# Sheet1.net
KiCad netlist of a schematic drawn in Altium Designer
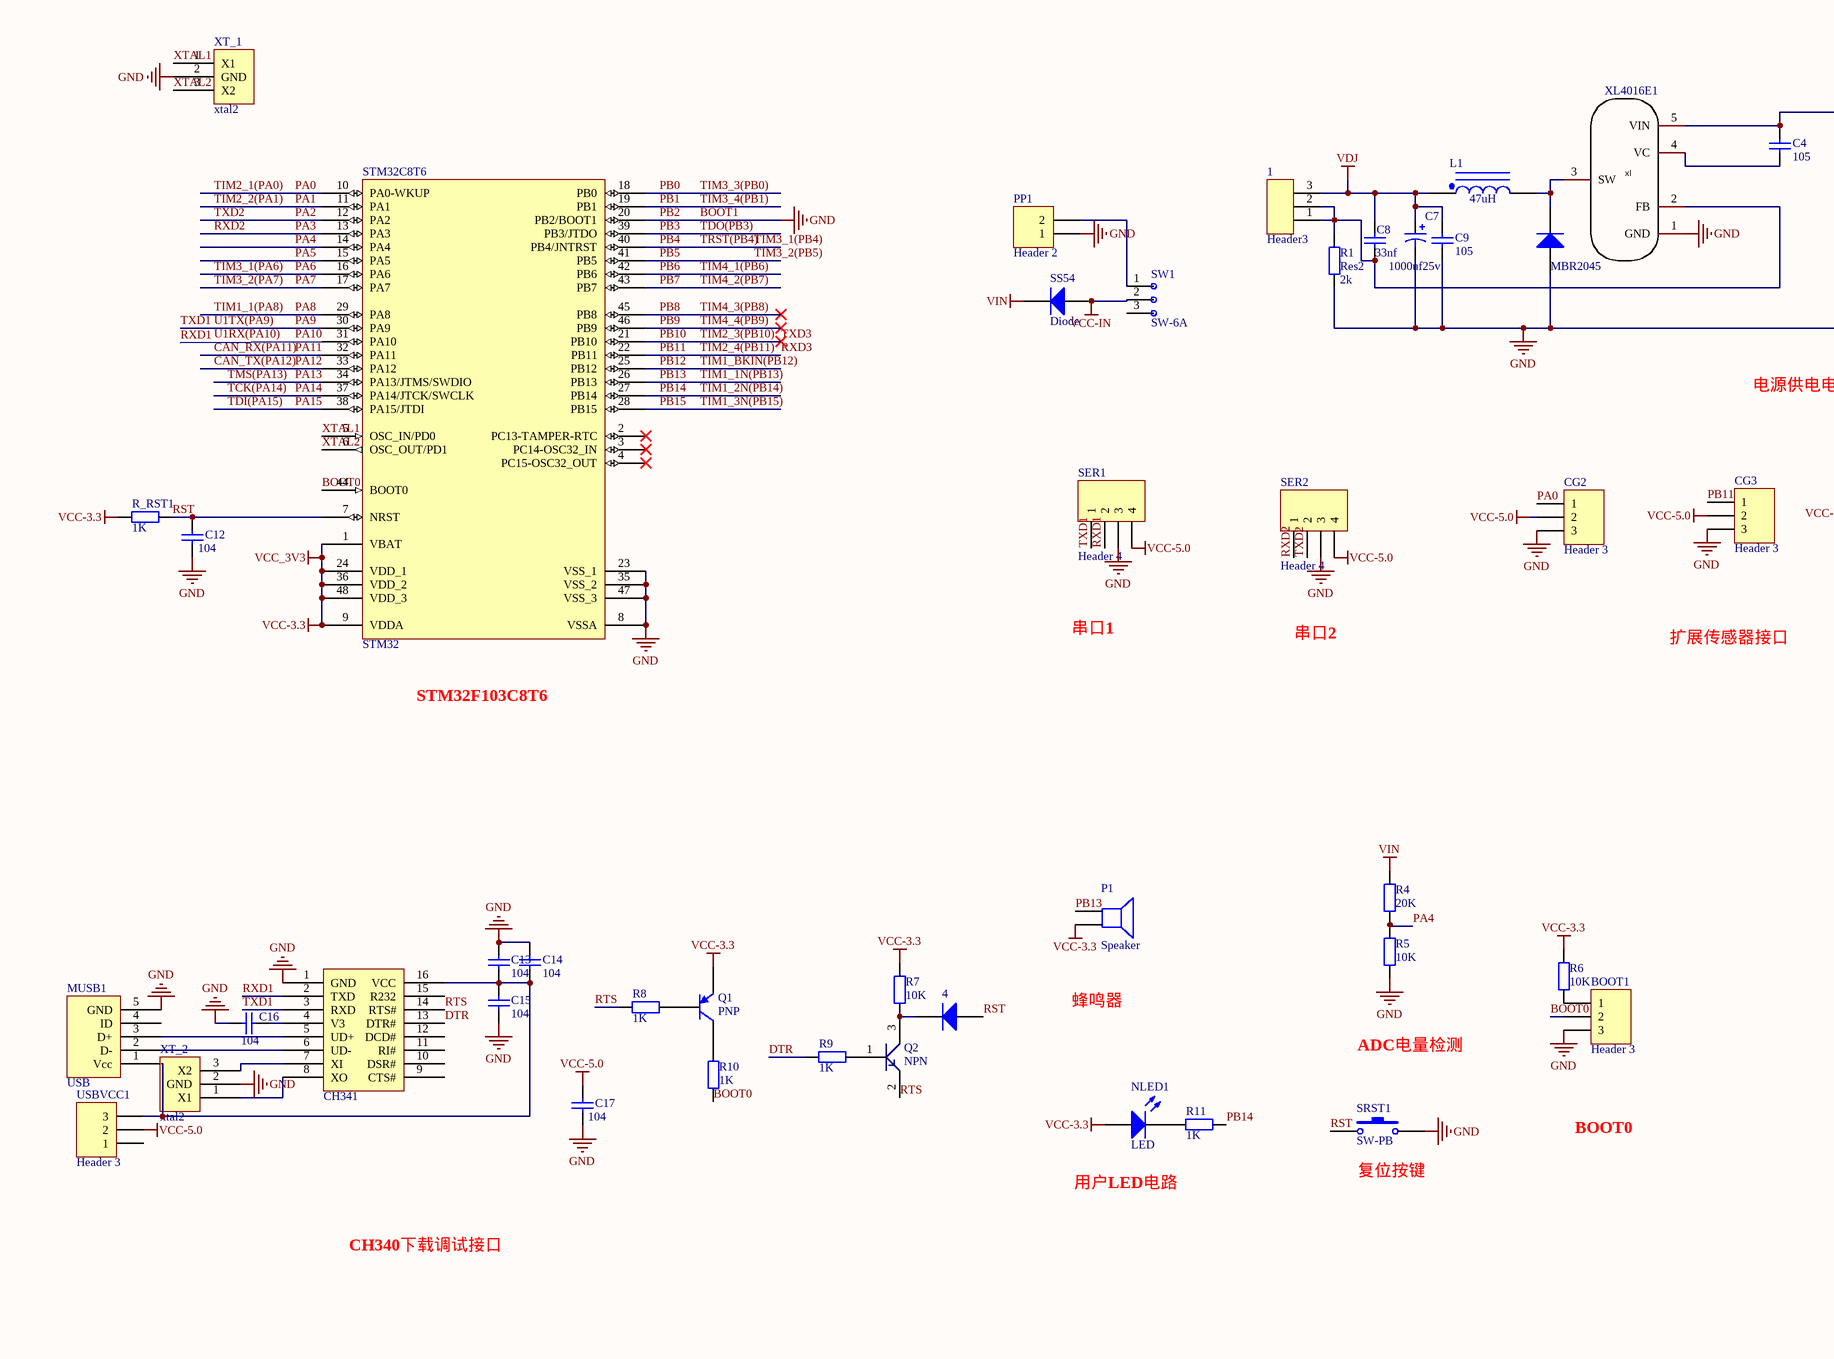
[diagram p0: Sheet1.SchDoc, left]
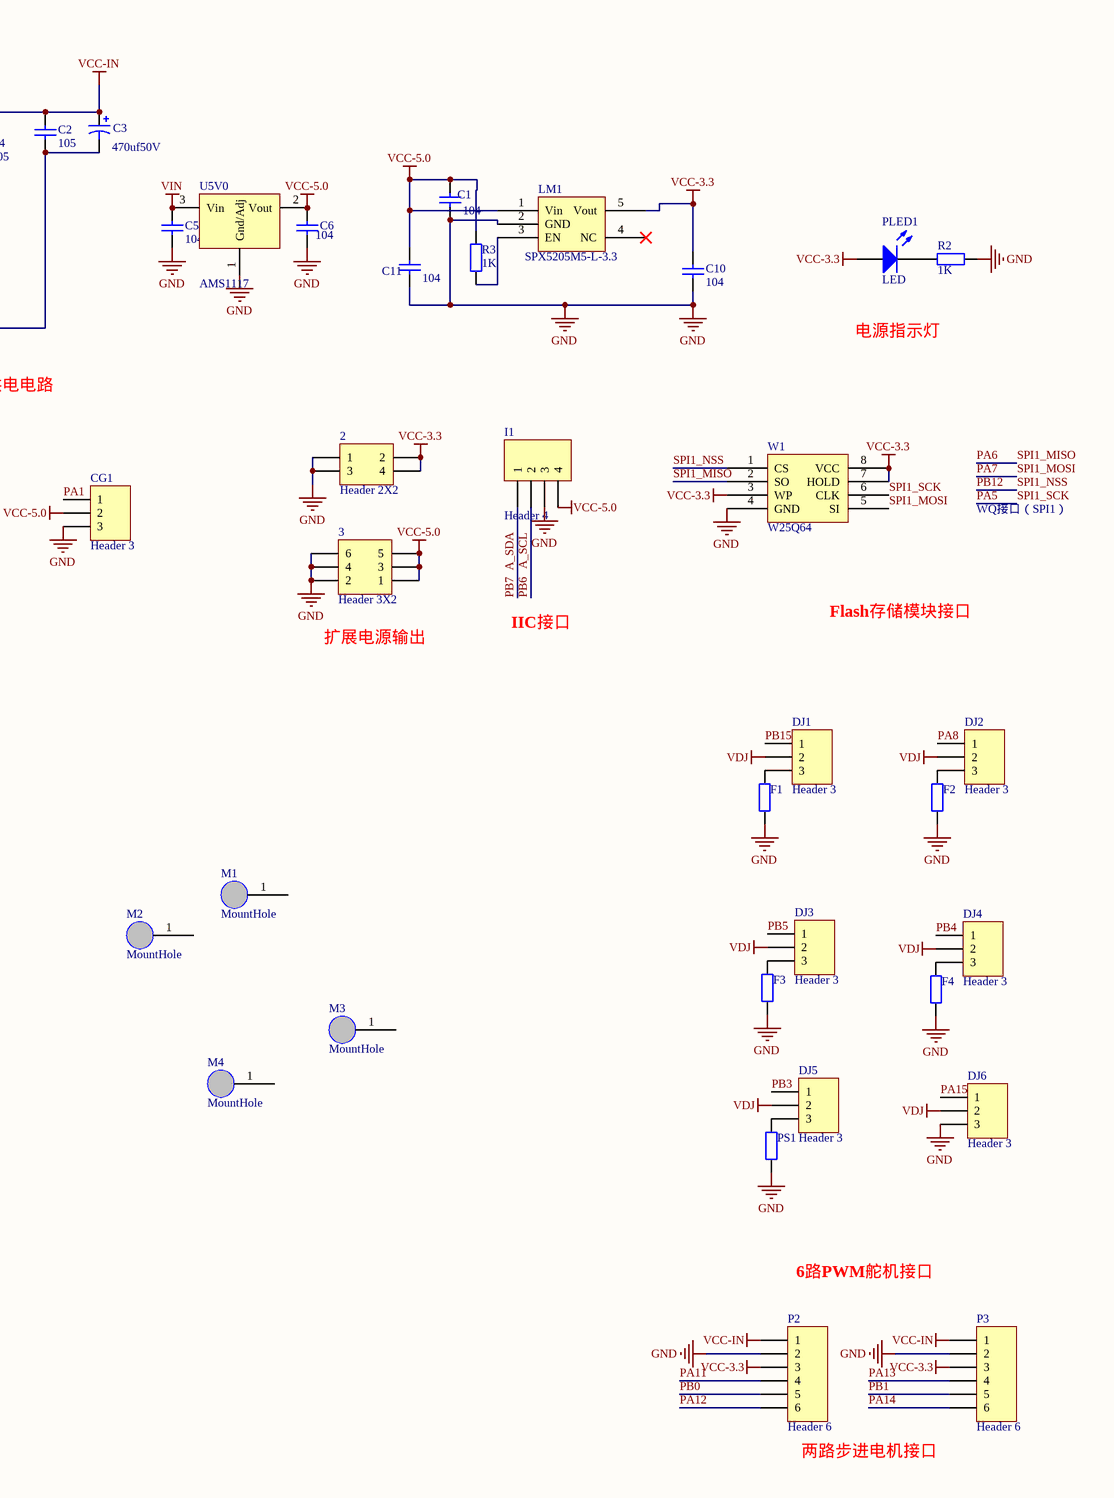
[diagram p1: Sheet1.SchDoc, right]

(export (version "E")
  (design (tool "Eeschema 10.0.6"))
  (components
    (comp (ref "1") (value "Header3") (footprint "pot（长方形）") (libsource (lib "MY-SCH") (part "Header3")))
    (comp (ref "2")
      (value "Header 2X2")
      (footprint "HDR2X2")
      (description "Header, 2-Pin, Dual row")
      (fields (field (name "PUBLISHER") "Altium Limited"))
      (libsource (lib "Miscellaneous Connectors") (part "Header 2X2"))
    )
    (comp (ref "3")
      (value "Header 3X2")
      (footprint "HDR2X3")
      (description "Header, 3-Pin, Dual row")
      (fields (field (name "PUBLISHER") "Altium Limited"))
      (libsource (lib "Miscellaneous Connectors") (part "Header 3X2"))
    )
    (comp (ref "4")
      (value "Diode 1N4007")
      (footprint "0805L")
      (description "1 Amp General Purpose Rectifier")
      (fields (field (name "PUBLISHER") "Altium Limited"))
      (libsource (lib "MY-SCH") (part "Diode 1N4007"))
    )
    (comp (ref "BOOT1")
      (value "Header 3")
      (footprint "HDR1X3")
      (description "Header, 3-Pin")
      (fields (field (name "PUBLISHER") "Altium Limited"))
      (libsource (lib "Miscellaneous Connectors") (part "Header 3"))
    )
    (comp (ref "C1")
      (value "104")
      (footprint "0603C")
      (description "Capacitor")
      (fields (field (name "Comment") "Cap") (field (name "PUBLISHER") "Altium Limited"))
      (libsource (lib "Miscellaneous Devices") (part "Cap"))
    )
    (comp (ref "C2")
      (value "105")
      (footprint "0603C")
      (description "Capacitor")
      (fields (field (name "Comment") "Cap") (field (name "PUBLISHER") "Altium Limited"))
      (libsource (lib "Miscellaneous Devices") (part "Cap"))
    )
    (comp (ref "C3")
      (value "470uf50V")
      (footprint "CAP_10_TIE")
      (description "Polarized Capacitor (Radial)")
      (fields (field (name "Comment") "Cap Pol1") (field (name "PUBLISHER") "Altium Limited"))
      (libsource (lib "Miscellaneous Devices") (part "Cap Pol1"))
    )
    (comp (ref "C4")
      (value "105")
      (footprint "0603C")
      (description "Capacitor")
      (fields (field (name "Comment") "Cap") (field (name "PUBLISHER") "Altium Limited"))
      (libsource (lib "Miscellaneous Devices") (part "Cap"))
    )
    (comp (ref "C5")
      (value "104")
      (footprint "0603C")
      (description "Capacitor")
      (fields (field (name "Comment") "Cap") (field (name "PUBLISHER") "Altium Limited"))
      (libsource (lib "Miscellaneous Devices") (part "Cap"))
    )
    (comp (ref "C6")
      (value "104")
      (footprint "0603C")
      (description "Capacitor")
      (fields (field (name "Comment") "Cap") (field (name "PUBLISHER") "Altium Limited"))
      (libsource (lib "Miscellaneous Devices") (part "Cap"))
    )
    (comp (ref "C7") (value "1000uf25v") (footprint "cap_6.3_tie") (libsource (lib "集成库") (part "Cap_Pol")))
    (comp (ref "C8")
      (value "33nf")
      (footprint "0603C")
      (description "Capacitor")
      (fields (field (name "Comment") "Cap") (field (name "PUBLISHER") "Altium Limited"))
      (libsource (lib "Miscellaneous Devices") (part "Cap"))
    )
    (comp (ref "C9")
      (value "105")
      (footprint "0603C")
      (description "Capacitor")
      (fields (field (name "Comment") "Cap") (field (name "PUBLISHER") "Altium Limited"))
      (libsource (lib "Miscellaneous Devices") (part "Cap"))
    )
    (comp (ref "C10")
      (value "104")
      (footprint "0603C")
      (description "Capacitor")
      (fields (field (name "Comment") "Cap") (field (name "PUBLISHER") "Altium Limited"))
      (libsource (lib "Miscellaneous Devices") (part "Cap"))
    )
    (comp (ref "C11")
      (value "104")
      (footprint "0603C")
      (description "Capacitor")
      (fields (field (name "Comment") "Cap") (field (name "PUBLISHER") "Altium Limited"))
      (libsource (lib "Miscellaneous Devices") (part "Cap"))
    )
    (comp (ref "C12")
      (value "104")
      (footprint "0603C")
      (description "Capacitor")
      (fields (field (name "Comment") "Cap") (field (name "PUBLISHER") "Altium Limited"))
      (libsource (lib "Miscellaneous Devices") (part "Cap"))
    )
    (comp (ref "C13")
      (value "104")
      (footprint "0603C")
      (description "Capacitor")
      (fields (field (name "Comment") "Cap") (field (name "PUBLISHER") "Altium Limited"))
      (libsource (lib "Miscellaneous Devices") (part "Cap"))
    )
    (comp (ref "C14")
      (value "104")
      (footprint "0603C")
      (description "Capacitor")
      (fields (field (name "Comment") "Cap") (field (name "PUBLISHER") "Altium Limited"))
      (libsource (lib "Miscellaneous Devices") (part "Cap"))
    )
    (comp (ref "C15")
      (value "104")
      (footprint "0603C")
      (description "Capacitor")
      (fields (field (name "Comment") "Cap") (field (name "PUBLISHER") "Altium Limited"))
      (libsource (lib "Miscellaneous Devices") (part "Cap"))
    )
    (comp (ref "C16")
      (value "104")
      (footprint "0603C")
      (description "Capacitor")
      (fields (field (name "Comment") "Cap") (field (name "PUBLISHER") "Altium Limited"))
      (libsource (lib "Miscellaneous Devices") (part "Cap"))
    )
    (comp (ref "C17")
      (value "104")
      (footprint "0603C")
      (description "Capacitor")
      (fields (field (name "Comment") "Cap") (field (name "PUBLISHER") "Altium Limited"))
      (libsource (lib "Miscellaneous Devices") (part "Cap"))
    )
    (comp (ref "CG1")
      (value "Header 3")
      (footprint "HDR1X3")
      (description "Header, 3-Pin")
      (fields (field (name "PUBLISHER") "Altium Limited"))
      (libsource (lib "Miscellaneous Connectors") (part "Header 3"))
    )
    (comp (ref "CG2")
      (value "Header 3")
      (footprint "HDR1X3")
      (description "Header, 3-Pin")
      (fields (field (name "PUBLISHER") "Altium Limited"))
      (libsource (lib "Miscellaneous Connectors") (part "Header 3"))
    )
    (comp (ref "CG3")
      (value "Header 3")
      (footprint "HDR1X3")
      (description "Header, 3-Pin")
      (fields (field (name "PUBLISHER") "Altium Limited"))
      (libsource (lib "Miscellaneous Connectors") (part "Header 3"))
    )
    (comp (ref "CH1") (value "CH341") (footprint "SOP16") (libsource (lib "DYS.SCHL1") (part "CH341")))
    (comp (ref "DJ1")
      (value "Header 3")
      (footprint "HDR1X3")
      (description "Header, 3-Pin")
      (fields (field (name "PUBLISHER") "Altium Limited"))
      (libsource (lib "Miscellaneous Connectors") (part "Header 3"))
    )
    (comp (ref "DJ2")
      (value "Header 3")
      (footprint "HDR1X3")
      (description "Header, 3-Pin")
      (fields (field (name "PUBLISHER") "Altium Limited"))
      (libsource (lib "Miscellaneous Connectors") (part "Header 3"))
    )
    (comp (ref "DJ3")
      (value "Header 3")
      (footprint "HDR1X3")
      (description "Header, 3-Pin")
      (fields (field (name "PUBLISHER") "Altium Limited"))
      (libsource (lib "Miscellaneous Connectors") (part "Header 3"))
    )
    (comp (ref "DJ4")
      (value "Header 3")
      (footprint "HDR1X3")
      (description "Header, 3-Pin")
      (fields (field (name "PUBLISHER") "Altium Limited"))
      (libsource (lib "Miscellaneous Connectors") (part "Header 3"))
    )
    (comp (ref "DJ5")
      (value "Header 3")
      (footprint "HDR1X3")
      (description "Header, 3-Pin")
      (fields (field (name "PUBLISHER") "Altium Limited"))
      (libsource (lib "Miscellaneous Connectors") (part "Header 3"))
    )
    (comp (ref "DJ6")
      (value "Header 3")
      (footprint "HDR1X3")
      (description "Header, 3-Pin")
      (fields (field (name "PUBLISHER") "Altium Limited"))
      (libsource (lib "Miscellaneous Connectors") (part "Header 3"))
    )
    (comp (ref "F1")
      (value "Res2")
      (footprint "0805R")
      (description "Resistor")
      (fields (field (name "PUBLISHER") "Altium Limited"))
      (libsource (lib "Miscellaneous Devices") (part "Res2"))
    )
    (comp (ref "F2")
      (value "Res2")
      (footprint "0805R")
      (description "Resistor")
      (fields (field (name "PUBLISHER") "Altium Limited"))
      (libsource (lib "Miscellaneous Devices") (part "Res2"))
    )
    (comp (ref "F3")
      (value "Res2")
      (footprint "0805R")
      (description "Resistor")
      (fields (field (name "PUBLISHER") "Altium Limited"))
      (libsource (lib "Miscellaneous Devices") (part "Res2"))
    )
    (comp (ref "F4")
      (value "Res2")
      (footprint "0805R")
      (description "Resistor")
      (fields (field (name "PUBLISHER") "Altium Limited"))
      (libsource (lib "Miscellaneous Devices") (part "Res2"))
    )
    (comp (ref "I1")
      (value "Header 4")
      (footprint "HDR1X4")
      (description "Header, 4-Pin")
      (fields (field (name "PUBLISHER") "Altium Limited"))
      (libsource (lib "Miscellaneous Connectors") (part "Header 4"))
    )
    (comp (ref "L1")
      (value "47uH")
      (footprint "L_8x15")
      (description "Magnetic-Core Inductor with Winding Polarity Marking")
      (fields (field (name "Comment") "Inductor Iron Dot") (field (name "PUBLISHER") "Altium Limited"))
      (libsource (lib "Miscellaneous Devices") (part "Inductor Iron Dot"))
    )
    (comp (ref "LM1")
      (value "SPX5205M5-L-3.3")
      (footprint "spx520")
      (libsource (lib "DYS.SCHL1") (part "SPX5205M5-L-5-0"))
    )
    (comp (ref "M1")
      (value "MountHole")
      (footprint "M3-MountSlot")
      (description "固定孔")
      (libsource (lib "DRV8701E 双驱V1.1 集成封装库") (part "MountHole"))
    )
    (comp (ref "M2")
      (value "MountHole")
      (footprint "M3-MountSlot")
      (description "固定孔")
      (libsource (lib "DRV8701E 双驱V1.1 集成封装库") (part "MountHole"))
    )
    (comp (ref "M3")
      (value "MountHole")
      (footprint "M3-MountSlot")
      (description "固定孔")
      (libsource (lib "DRV8701E 双驱V1.1 集成封装库") (part "MountHole"))
    )
    (comp (ref "M4")
      (value "MountHole")
      (footprint "M3-MountSlot")
      (description "固定孔")
      (libsource (lib "DRV8701E 双驱V1.1 集成封装库") (part "MountHole"))
    )
    (comp (ref "MBR2045")
      (value "Diode 1N4007")
      (footprint "SS54")
      (description "1 Amp General Purpose Rectifier")
      (fields (field (name "PUBLISHER") "Altium Limited"))
      (libsource (lib "MY-SCH") (part "Diode 1N4007"))
    )
    (comp (ref "MUSB1") (value "USB") (footprint "microMINIusb 2") (libsource (lib "DYS.SCHL1") (part "USB")))
    (comp (ref "NLED1") (value "LED") (footprint "0603L") (libsource (lib "MY-SCH") (part "LED")))
    (comp (ref "P1")
      (value "Speaker")
      (footprint "beep_9mm")
      (description "Loudspeaker")
      (fields (field (name "PUBLISHER") "Altium Limited"))
      (libsource (lib "Miscellaneous Devices") (part "Speaker"))
    )
    (comp (ref "P2")
      (value "Header 6")
      (footprint "HDR1X6")
      (description "Header, 6-Pin")
      (fields (field (name "PUBLISHER") "Altium Limited"))
      (libsource (lib "Miscellaneous Connectors") (part "Header 6"))
    )
    (comp (ref "P3")
      (value "Header 6")
      (footprint "HDR1X6")
      (description "Header, 6-Pin")
      (fields (field (name "PUBLISHER") "Altium Limited"))
      (libsource (lib "Miscellaneous Connectors") (part "Header 6"))
    )
    (comp (ref "PLED1") (value "LED") (footprint "0603L") (libsource (lib "MY-SCH") (part "LED")))
    (comp (ref "PP1")
      (value "Header 2")
      (footprint "接线柱_2")
      (description "Header, 2-Pin")
      (fields (field (name "PUBLISHER") "Altium Limited"))
      (libsource (lib "Miscellaneous Connectors") (part "Header 2"))
    )
    (comp (ref "PS1")
      (value "Res2")
      (footprint "0805R")
      (description "Resistor")
      (fields (field (name "PUBLISHER") "Altium Limited"))
      (libsource (lib "Miscellaneous Devices") (part "Res2"))
    )
    (comp (ref "Q1") (value "PNP") (footprint "sot-23") (libsource (lib "mysch") (part "PNP")))
    (comp (ref "Q2") (value "NPN") (footprint "sot-23") (libsource (lib "mysch") (part "NPN")))
    (comp (ref "R1")
      (value "Res2")
      (footprint "0603R")
      (description "Resistor")
      (fields (field (name "ALTIUM_VALUE") "2k") (field (name "PUBLISHER") "Altium Limited"))
      (libsource (lib "") (part "Res2_1"))
    )
    (comp (ref "R2")
      (value "1K")
      (footprint "0603R")
      (description "Resistor")
      (fields (field (name "Comment") "Res2") (field (name "PUBLISHER") "Altium Limited"))
      (libsource (lib "") (part "Res2_3"))
    )
    (comp (ref "R3")
      (value "1K")
      (footprint "0603R")
      (description "Resistor")
      (fields (field (name "Comment") "Res2") (field (name "PUBLISHER") "Altium Limited"))
      (libsource (lib "") (part "Res2_1"))
    )
    (comp (ref "R4")
      (value "20K")
      (footprint "0603R")
      (description "Resistor")
      (fields (field (name "Comment") "Res2") (field (name "PUBLISHER") "Altium Limited"))
      (libsource (lib "") (part "Res2_1"))
    )
    (comp (ref "R5")
      (value "10K")
      (footprint "0603R")
      (description "Resistor")
      (fields (field (name "Comment") "Res2") (field (name "PUBLISHER") "Altium Limited"))
      (libsource (lib "") (part "Res2_1"))
    )
    (comp (ref "R6")
      (value "10K")
      (footprint "0603R")
      (description "Resistor")
      (fields (field (name "Comment") "Res2") (field (name "PUBLISHER") "Altium Limited"))
      (libsource (lib "") (part "Res2_1"))
    )
    (comp (ref "R7")
      (value "10K")
      (footprint "0603R")
      (description "Resistor")
      (fields (field (name "Comment") "Res2") (field (name "PUBLISHER") "Altium Limited"))
      (libsource (lib "") (part "Res2_1"))
    )
    (comp (ref "R8")
      (value "1K")
      (footprint "0603R")
      (description "Resistor")
      (fields (field (name "Comment") "Res2") (field (name "PUBLISHER") "Altium Limited"))
      (libsource (lib "") (part "Res2_2"))
    )
    (comp (ref "R9")
      (value "1K")
      (footprint "0603R")
      (description "Resistor")
      (fields (field (name "Comment") "Res2") (field (name "PUBLISHER") "Altium Limited"))
      (libsource (lib "") (part "Res2_3"))
    )
    (comp (ref "R10")
      (value "1K")
      (footprint "0603R")
      (description "Resistor")
      (fields (field (name "Comment") "Res2") (field (name "PUBLISHER") "Altium Limited"))
      (libsource (lib "Miscellaneous Devices") (part "Res2"))
    )
    (comp (ref "R11")
      (value "1K")
      (footprint "0603R")
      (description "Resistor")
      (fields (field (name "Comment") "Res2") (field (name "PUBLISHER") "Altium Limited"))
      (libsource (lib "") (part "Res2_3"))
    )
    (comp (ref "R_RST1")
      (value "1K")
      (footprint "0603R")
      (description "Resistor")
      (fields (field (name "Comment") "Res2") (field (name "PUBLISHER") "Altium Limited"))
      (libsource (lib "") (part "Res2_2"))
    )
    (comp (ref "SER1")
      (value "Header 4")
      (footprint "HDR1X4")
      (description "Header, 4-Pin")
      (fields (field (name "PUBLISHER") "Altium Limited"))
      (libsource (lib "Miscellaneous Connectors") (part "Header 4"))
    )
    (comp (ref "SER2")
      (value "Header 4")
      (footprint "HDR1X4")
      (description "Header, 4-Pin")
      (fields (field (name "PUBLISHER") "Altium Limited"))
      (libsource (lib "Miscellaneous Connectors") (part "Header 4"))
    )
    (comp (ref "SRST1") (value "SW-PB") (footprint "miniBUTTON") (libsource (lib "arduinoV1") (part "SW-PB")))
    (comp (ref "SS54")
      (value "Diode")
      (footprint "贴片_4007")
      (description "Default Diode")
      (fields (field (name "PUBLISHER") "Altium Limited"))
      (libsource (lib "SPP_V1") (part "Diode"))
    )
    (comp (ref "STM32C8T6")
      (value "STM32")
      (footprint "LQFP48")
      (libsource (lib "2013机器人队元件标准库") (part "STM32F103C8T6"))
    )
    (comp (ref "SW1") (value "SW-6A") (footprint "SW-6A") (libsource (lib "mysch") (part "SW-6A")))
    (comp (ref "U5V0") (value "AMS1117") (footprint "sot-223") (libsource (lib "MY-SCH") (part "AMS1117")))
    (comp (ref "USBVCC1")
      (value "Header 3")
      (footprint "HDR1X3")
      (description "Header, 3-Pin")
      (fields (field (name "PUBLISHER") "Altium Limited"))
      (libsource (lib "") (part "Header 3_1"))
    )
    (comp (ref "W1") (value "W25Q64") (footprint "sop8 - kuan") (libsource (lib "MY-SCH") (part "W25Q64")))
    (comp (ref "xl")
      (value "XL4016E1")
      (footprint "PCBComponent_1")
      (fields (field (name "MANUFACTURER") "XLSEMI(芯龙)"))
      (libsource (lib "altium-import") (part "root_0_XL4016E1_"))
    )
    (comp (ref "XT_1") (value "xtal2") (footprint "XTAL_3213") (libsource (lib "MY-SCH") (part "xtal2")))
    (comp (ref "XT_2") (value "xtal2") (footprint "XTAL_3213") (libsource (lib "") (part "xtal2_1")))
  )
  (nets
    (net (code "1") (name "/A_SCL") (class "Default")
      (node (ref "I1") (pin "2") (pinfunction "2_2") (pintype "passive"))
      (node (ref "STM32C8T6") (pin "42") (pinfunction "PB6_42") (pintype "bidirectional"))
    )
    (net (code "2") (name "/A_SDA") (class "Default")
      (node (ref "I1") (pin "1") (pinfunction "1_1") (pintype "passive"))
      (node (ref "STM32C8T6") (pin "43") (pinfunction "PB7_43") (pintype "bidirectional"))
    )
    (net (code "3") (name "/BOOT0") (class "Default")
      (node (ref "BOOT1") (pin "2") (pinfunction "2_2") (pintype "passive"))
      (node (ref "R10") (pin "1") (pinfunction "1_1") (pintype "passive"))
      (node (ref "STM32C8T6") (pin "44") (pinfunction "BOOT0_44") (pintype "input"))
    )
    (net (code "4") (name "/CAN_RX(PA11)") (class "Default")
      (node (ref "P2") (pin "4") (pinfunction "4_4") (pintype "passive"))
      (node (ref "STM32C8T6") (pin "32") (pinfunction "PA11_32") (pintype "bidirectional"))
    )
    (net (code "5") (name "/CAN_TX(PA12)") (class "Default")
      (node (ref "P2") (pin "6") (pinfunction "6_6") (pintype "passive"))
      (node (ref "STM32C8T6") (pin "33") (pinfunction "PA12_33") (pintype "bidirectional"))
    )
    (net (code "6") (name "/DTR") (class "Default")
      (node (ref "CH1") (pin "13") (pinfunction "DTR#_13") (pintype "passive"))
      (node (ref "R9") (pin "2") (pinfunction "2_2") (pintype "passive"))
    )
    (net (code "7") (name "/PA0") (class "Default")
      (node (ref "CG2") (pin "1") (pinfunction "1_1") (pintype "passive"))
      (node (ref "STM32C8T6") (pin "10") (pinfunction "PA0-WKUP_10") (pintype "bidirectional"))
    )
    (net (code "8") (name "/PA1") (class "Default")
      (node (ref "CG1") (pin "1") (pinfunction "1_1") (pintype "passive"))
      (node (ref "STM32C8T6") (pin "11") (pinfunction "PA1_11") (pintype "bidirectional"))
    )
    (net (code "9") (name "/PA2") (class "Default")
      (node (ref "SER2") (pin "2") (pinfunction "2_2") (pintype "passive"))
      (node (ref "STM32C8T6") (pin "12") (pinfunction "PA2_12") (pintype "bidirectional"))
    )
    (net (code "10") (name "/PA3") (class "Default")
      (node (ref "SER2") (pin "1") (pinfunction "1_1") (pintype "passive"))
      (node (ref "STM32C8T6") (pin "13") (pinfunction "PA3_13") (pintype "bidirectional"))
    )
    (net (code "11") (name "/PA4") (class "Default")
      (node (ref "R4") (pin "2") (pinfunction "2_2") (pintype "passive"))
      (node (ref "R5") (pin "1") (pinfunction "1_1") (pintype "passive"))
      (node (ref "STM32C8T6") (pin "14") (pinfunction "PA4_14") (pintype "bidirectional"))
    )
    (net (code "12") (name "/PA5") (class "Default")
      (node (ref "STM32C8T6") (pin "15") (pinfunction "PA5_15") (pintype "bidirectional"))
      (node (ref "W1") (pin "6") (pinfunction "CLK_6") (pintype "passive"))
    )
    (net (code "13") (name "/PA6") (class "Default")
      (node (ref "STM32C8T6") (pin "16") (pinfunction "PA6_16") (pintype "bidirectional"))
      (node (ref "W1") (pin "2") (pinfunction "SO_2") (pintype "passive"))
    )
    (net (code "14") (name "/PA7") (class "Default")
      (node (ref "STM32C8T6") (pin "17") (pinfunction "PA7_17") (pintype "bidirectional"))
      (node (ref "W1") (pin "5") (pinfunction "SI_5") (pintype "passive"))
    )
    (net (code "15") (name "/PA8") (class "Default")
      (node (ref "DJ2") (pin "1") (pinfunction "1_1") (pintype "passive"))
      (node (ref "STM32C8T6") (pin "29") (pinfunction "PA8_29") (pintype "bidirectional"))
    )
    (net (code "16") (name "/PA9") (class "Default")
      (node (ref "CH1") (pin "3") (pinfunction "RXD_3") (pintype "passive"))
      (node (ref "SER1") (pin "1") (pinfunction "1_1") (pintype "passive"))
      (node (ref "STM32C8T6") (pin "30") (pinfunction "PA9_30") (pintype "bidirectional"))
    )
    (net (code "18") (name "/PA13") (class "Default")
      (node (ref "P3") (pin "4") (pinfunction "4_4") (pintype "passive"))
      (node (ref "STM32C8T6") (pin "34") (pinfunction "PA13/JTMS/SWDIO_34") (pintype "bidirectional"))
    )
    (net (code "19") (name "/PA14") (class "Default")
      (node (ref "P3") (pin "6") (pinfunction "6_6") (pintype "passive"))
      (node (ref "STM32C8T6") (pin "37") (pinfunction "PA14/JTCK/SWCLK_37") (pintype "bidirectional"))
    )
    (net (code "20") (name "/PA15") (class "Default")
      (node (ref "DJ6") (pin "1") (pinfunction "1_1") (pintype "passive"))
      (node (ref "STM32C8T6") (pin "38") (pinfunction "PA15/JTDI_38") (pintype "bidirectional"))
    )
    (net (code "21") (name "/PB0") (class "Default")
      (node (ref "P2") (pin "5") (pinfunction "5_5") (pintype "passive"))
      (node (ref "STM32C8T6") (pin "18") (pinfunction "PB0_18") (pintype "bidirectional"))
    )
    (net (code "22") (name "/PB1") (class "Default")
      (node (ref "P3") (pin "5") (pinfunction "5_5") (pintype "passive"))
      (node (ref "STM32C8T6") (pin "19") (pinfunction "PB1_19") (pintype "bidirectional"))
    )
    (net (code "23") (name "/PB3") (class "Default")
      (node (ref "DJ5") (pin "1") (pinfunction "1_1") (pintype "passive"))
      (node (ref "STM32C8T6") (pin "39") (pinfunction "PB3/JTDO_39") (pintype "bidirectional"))
    )
    (net (code "24") (name "/PB4") (class "Default")
      (node (ref "DJ4") (pin "1") (pinfunction "1_1") (pintype "passive"))
      (node (ref "STM32C8T6") (pin "40") (pinfunction "PB4/JNTRST_40") (pintype "bidirectional"))
    )
    (net (code "25") (name "/PB5") (class "Default")
      (node (ref "DJ3") (pin "1") (pinfunction "1_1") (pintype "passive"))
      (node (ref "STM32C8T6") (pin "41") (pinfunction "PB5_41") (pintype "bidirectional"))
    )
    (net (code "26") (name "/PB8") (class "Default")
      (node (ref "STM32C8T6") (pin "45") (pinfunction "PB8_45") (pintype "bidirectional+no_connect"))
    )
    (net (code "27") (name "/PB9") (class "Default")
      (node (ref "STM32C8T6") (pin "46") (pinfunction "PB9_46") (pintype "bidirectional+no_connect"))
    )
    (net (code "28") (name "/PB10") (class "Default")
      (node (ref "STM32C8T6") (pin "21") (pinfunction "PB10_21") (pintype "bidirectional+no_connect"))
    )
    (net (code "29") (name "/PB11") (class "Default")
      (node (ref "CG3") (pin "1") (pinfunction "1_1") (pintype "passive"))
      (node (ref "STM32C8T6") (pin "22") (pinfunction "PB11_22") (pintype "bidirectional"))
    )
    (net (code "30") (name "/PB12") (class "Default")
      (node (ref "STM32C8T6") (pin "25") (pinfunction "PB12_25") (pintype "bidirectional"))
      (node (ref "W1") (pin "1") (pinfunction "CS_1") (pintype "passive"))
    )
    (net (code "31") (name "/PB13") (class "Default")
      (node (ref "P1") (pin "1") (pinfunction "1_1") (pintype "passive"))
      (node (ref "STM32C8T6") (pin "26") (pinfunction "PB13_26") (pintype "bidirectional"))
    )
    (net (code "32") (name "/PB14") (class "Default")
      (node (ref "R11") (pin "1") (pinfunction "1_1") (pintype "passive"))
      (node (ref "STM32C8T6") (pin "27") (pinfunction "PB14_27") (pintype "bidirectional"))
    )
    (net (code "33") (name "/PB15") (class "Default")
      (node (ref "DJ1") (pin "1") (pinfunction "1_1") (pintype "passive"))
      (node (ref "STM32C8T6") (pin "28") (pinfunction "PB15_28") (pintype "bidirectional"))
    )
    (net (code "34") (name "/RST") (class "Default")
      (node (ref "4") (pin "1") (pinfunction "A_1") (pintype "passive"))
      (node (ref "C12") (pin "2") (pinfunction "2_2") (pintype "passive"))
      (node (ref "R_RST1") (pin "2") (pinfunction "2_2") (pintype "passive"))
      (node (ref "SRST1") (pin "1") (pinfunction "1_1") (pintype "passive"))
      (node (ref "STM32C8T6") (pin "7") (pinfunction "NRST_7") (pintype "bidirectional"))
    )
    (net (code "35") (name "/RTS") (class "Default")
      (node (ref "CH1") (pin "14") (pinfunction "RTS#_14") (pintype "passive"))
      (node (ref "Q2") (pin "2") (pinfunction "2_2") (pintype "passive"))
      (node (ref "R8") (pin "1") (pinfunction "1_1") (pintype "passive"))
    )
    (net (code "36") (name "/RXD1") (class "Default")
      (node (ref "CH1") (pin "2") (pinfunction "TXD_2") (pintype "passive"))
      (node (ref "SER1") (pin "2") (pinfunction "2_2") (pintype "passive"))
      (node (ref "STM32C8T6") (pin "31") (pinfunction "PA10_31") (pintype "bidirectional"))
    )
    (net (code "38") (name "/XTAL1") (class "Default")
      (node (ref "STM32C8T6") (pin "5") (pinfunction "OSC_IN/PD0_5") (pintype "input"))
      (node (ref "XT_1") (pin "1") (pinfunction "X1_1") (pintype "passive"))
    )
    (net (code "39") (name "/XTAL2") (class "Default")
      (node (ref "STM32C8T6") (pin "6") (pinfunction "OSC_OUT/PD1_6") (pintype "output"))
      (node (ref "XT_1") (pin "3") (pinfunction "X2_3") (pintype "passive"))
    )
    (net (code "40") (name "GND") (class "Default")
      (node (ref "2") (pin "1") (pinfunction "1_1") (pintype "passive"))
      (node (ref "2") (pin "3") (pinfunction "3_3") (pintype "passive"))
      (node (ref "3") (pin "2") (pinfunction "2_2") (pintype "passive"))
      (node (ref "3") (pin "4") (pinfunction "4_4") (pintype "passive"))
      (node (ref "3") (pin "6") (pinfunction "6_6") (pintype "passive"))
      (node (ref "BOOT1") (pin "3") (pinfunction "3_3") (pintype "passive"))
      (node (ref "C1") (pin "1") (pinfunction "1_1") (pintype "passive"))
      (node (ref "C10") (pin "1") (pinfunction "1_1") (pintype "passive"))
      (node (ref "C11") (pin "1") (pinfunction "1_1") (pintype "passive"))
      (node (ref "C12") (pin "1") (pinfunction "1_1") (pintype "passive"))
      (node (ref "C13") (pin "2") (pinfunction "2_2") (pintype "passive"))
      (node (ref "C14") (pin "2") (pinfunction "2_2") (pintype "passive"))
      (node (ref "C15") (pin "2") (pinfunction "2_2") (pintype "passive"))
      (node (ref "C16") (pin "2") (pinfunction "2_2") (pintype "passive"))
      (node (ref "C17") (pin "1") (pinfunction "1_1") (pintype "passive"))
      (node (ref "C2") (pin "2") (pinfunction "2_2") (pintype "passive"))
      (node (ref "C3") (pin "2") (pinfunction "2_2") (pintype "passive"))
      (node (ref "C5") (pin "1") (pinfunction "1_1") (pintype "passive"))
      (node (ref "C6") (pin "1") (pinfunction "1_1") (pintype "passive"))
      (node (ref "C7") (pin "2") (pinfunction "2_2") (pintype "passive"))
      (node (ref "C9") (pin "2") (pinfunction "2_2") (pintype "passive"))
      (node (ref "CG1") (pin "3") (pinfunction "3_3") (pintype "passive"))
      (node (ref "CG2") (pin "3") (pinfunction "3_3") (pintype "passive"))
      (node (ref "CG3") (pin "3") (pinfunction "3_3") (pintype "passive"))
      (node (ref "CH1") (pin "1") (pinfunction "GND_1") (pintype "passive"))
      (node (ref "DJ6") (pin "3") (pinfunction "3_3") (pintype "passive"))
      (node (ref "F1") (pin "1") (pinfunction "1_1") (pintype "passive"))
      (node (ref "F2") (pin "1") (pinfunction "1_1") (pintype "passive"))
      (node (ref "F3") (pin "1") (pinfunction "1_1") (pintype "passive"))
      (node (ref "F4") (pin "1") (pinfunction "1_1") (pintype "passive"))
      (node (ref "I1") (pin "3") (pinfunction "3_3") (pintype "passive"))
      (node (ref "LM1") (pin "2") (pinfunction "GND_2") (pintype "passive"))
      (node (ref "MBR2045") (pin "1") (pinfunction "A_1") (pintype "passive"))
      (node (ref "MUSB1") (pin "5") (pinfunction "GND_5") (pintype "passive"))
      (node (ref "P2") (pin "2") (pinfunction "2_2") (pintype "passive"))
      (node (ref "P3") (pin "2") (pinfunction "2_2") (pintype "passive"))
      (node (ref "PP1") (pin "1") (pinfunction "1_1") (pintype "passive"))
      (node (ref "PS1") (pin "1") (pinfunction "1_1") (pintype "passive"))
      (node (ref "R1") (pin "2") (pinfunction "2_2") (pintype "passive"))
      (node (ref "R2") (pin "1") (pinfunction "1_1") (pintype "passive"))
      (node (ref "R5") (pin "2") (pinfunction "2_2") (pintype "passive"))
      (node (ref "SER1") (pin "3") (pinfunction "3_3") (pintype "passive"))
      (node (ref "SER2") (pin "3") (pinfunction "3_3") (pintype "passive"))
      (node (ref "SRST1") (pin "2") (pinfunction "2_2") (pintype "passive"))
      (node (ref "STM32C8T6") (pin "20") (pinfunction "PB2/BOOT1_20") (pintype "bidirectional"))
      (node (ref "STM32C8T6") (pin "23") (pinfunction "VSS_1_23") (pintype "power_in"))
      (node (ref "STM32C8T6") (pin "35") (pinfunction "VSS_2_35") (pintype "power_in"))
      (node (ref "STM32C8T6") (pin "47") (pinfunction "VSS_3_47") (pintype "power_in"))
      (node (ref "STM32C8T6") (pin "8") (pinfunction "VSSA_8") (pintype "power_in"))
      (node (ref "U5V0") (pin "1") (pinfunction "Gnd/Adj_1") (pintype "passive"))
      (node (ref "W1") (pin "4") (pinfunction "GND_4") (pintype "passive"))
      (node (ref "XT_1") (pin "2") (pinfunction "GND_2") (pintype "passive"))
      (node (ref "XT_2") (pin "2") (pinfunction "GND_2") (pintype "passive"))
      (node (ref "xl") (pin "1") (pinfunction "GND_1") (pintype "passive"))
    )
    (net (code "41") (name "Net-(4-K)") (class "Default")
      (node (ref "4") (pin "2") (pinfunction "K_2") (pintype "passive"))
      (node (ref "Q2") (pin "3") (pinfunction "3_3") (pintype "passive"))
      (node (ref "R7") (pin "2") (pinfunction "2_2") (pintype "passive"))
    )
    (net (code "42") (name "Net-(BOOT1-Pad1)") (class "Default")
      (node (ref "BOOT1") (pin "1") (pinfunction "1_1") (pintype "passive"))
      (node (ref "R6") (pin "2") (pinfunction "2_2") (pintype "passive"))
    )
    (net (code "43") (name "Net-(CH1-UD+)") (class "Default")
      (node (ref "CH1") (pin "5") (pinfunction "UD+_5") (pintype "passive"))
      (node (ref "MUSB1") (pin "3") (pinfunction "D+_3") (pintype "passive"))
    )
    (net (code "44") (name "Net-(CH1-UD-)") (class "Default")
      (node (ref "CH1") (pin "6") (pinfunction "UD-_6") (pintype "passive"))
      (node (ref "MUSB1") (pin "2") (pinfunction "D-_2") (pintype "passive"))
    )
    (net (code "45") (name "Net-(CH1-V3)") (class "Default")
      (node (ref "C16") (pin "1") (pinfunction "1_1") (pintype "passive"))
      (node (ref "CH1") (pin "4") (pinfunction "V3_4") (pintype "passive"))
    )
    (net (code "46") (name "Net-(CH1-VCC)") (class "Default")
      (node (ref "C13") (pin "1") (pinfunction "1_1") (pintype "passive"))
      (node (ref "C14") (pin "1") (pinfunction "1_1") (pintype "passive"))
      (node (ref "C15") (pin "1") (pinfunction "1_1") (pintype "passive"))
      (node (ref "CH1") (pin "16") (pinfunction "VCC_16") (pintype "passive"))
      (node (ref "MUSB1") (pin "1") (pinfunction "Vcc_1") (pintype "passive"))
      (node (ref "USBVCC1") (pin "3") (pinfunction "3_3") (pintype "passive"))
    )
    (net (code "47") (name "Net-(CH1-XI)") (class "Default")
      (node (ref "CH1") (pin "7") (pinfunction "XI_7") (pintype "passive"))
      (node (ref "XT_2") (pin "3") (pinfunction "X2_3") (pintype "passive"))
    )
    (net (code "48") (name "Net-(CH1-XO)") (class "Default")
      (node (ref "CH1") (pin "8") (pinfunction "XO_8") (pintype "passive"))
      (node (ref "XT_2") (pin "1") (pinfunction "X1_1") (pintype "passive"))
    )
    (net (code "49") (name "Net-(DJ1-Pad3)") (class "Default")
      (node (ref "DJ1") (pin "3") (pinfunction "3_3") (pintype "passive"))
      (node (ref "F1") (pin "2") (pinfunction "2_2") (pintype "passive"))
    )
    (net (code "50") (name "Net-(DJ2-Pad3)") (class "Default")
      (node (ref "DJ2") (pin "3") (pinfunction "3_3") (pintype "passive"))
      (node (ref "F2") (pin "2") (pinfunction "2_2") (pintype "passive"))
    )
    (net (code "51") (name "Net-(DJ3-Pad3)") (class "Default")
      (node (ref "DJ3") (pin "3") (pinfunction "3_3") (pintype "passive"))
      (node (ref "F3") (pin "2") (pinfunction "2_2") (pintype "passive"))
    )
    (net (code "52") (name "Net-(DJ4-Pad3)") (class "Default")
      (node (ref "DJ4") (pin "3") (pinfunction "3_3") (pintype "passive"))
      (node (ref "F4") (pin "2") (pinfunction "2_2") (pintype "passive"))
    )
    (net (code "53") (name "Net-(DJ5-Pad3)") (class "Default")
      (node (ref "DJ5") (pin "3") (pinfunction "3_3") (pintype "passive"))
      (node (ref "PS1") (pin "2") (pinfunction "2_2") (pintype "passive"))
    )
    (net (code "54") (name "Net-(LM1-EN)") (class "Default")
      (node (ref "LM1") (pin "3") (pinfunction "EN_3") (pintype "passive"))
      (node (ref "R3") (pin "2") (pinfunction "2_2") (pintype "passive"))
    )
    (net (code "55") (name "Net-(MBR2045-K)") (class "Default")
      (node (ref "L1") (pin "2") (pinfunction "2_2") (pintype "passive"))
      (node (ref "MBR2045") (pin "2") (pinfunction "K_2") (pintype "passive"))
      (node (ref "xl") (pin "3") (pinfunction "SW_3") (pintype "passive"))
    )
    (net (code "56") (name "Net-(NLED1-K)") (class "Default")
      (node (ref "NLED1") (pin "2") (pinfunction "K_2") (pintype "passive"))
      (node (ref "R11") (pin "2") (pinfunction "2_2") (pintype "passive"))
    )
    (net (code "57") (name "Net-(PLED1-K)") (class "Default")
      (node (ref "PLED1") (pin "2") (pinfunction "K_2") (pintype "passive"))
      (node (ref "R2") (pin "2") (pinfunction "2_2") (pintype "passive"))
    )
    (net (code "58") (name "Net-(PP1-Pad2)") (class "Default")
      (node (ref "PP1") (pin "2") (pinfunction "2_2") (pintype "passive"))
      (node (ref "SW1") (pin "1") (pinfunction "1_1") (pintype "passive"))
    )
    (net (code "59") (name "Net-(Q1-B)") (class "Default")
      (node (ref "Q1") (pin "1") (pinfunction "B_1") (pintype "passive"))
      (node (ref "R8") (pin "2") (pinfunction "2_2") (pintype "passive"))
    )
    (net (code "60") (name "Net-(Q1-C)") (class "Default")
      (node (ref "Q1") (pin "3") (pinfunction "C_3") (pintype "passive"))
      (node (ref "R10") (pin "2") (pinfunction "2_2") (pintype "passive"))
    )
    (net (code "61") (name "Net-(Q2-Pad1)") (class "Default")
      (node (ref "Q2") (pin "1") (pinfunction "1_1") (pintype "passive"))
      (node (ref "R9") (pin "1") (pinfunction "1_1") (pintype "passive"))
    )
    (net (code "62") (name "Net-(xl-FB)") (class "Default")
      (node (ref "1") (pin "1") (pinfunction "1_1") (pintype "passive"))
      (node (ref "1") (pin "2") (pinfunction "2_2") (pintype "passive"))
      (node (ref "C8") (pin "2") (pinfunction "2_2") (pintype "passive"))
      (node (ref "R1") (pin "1") (pinfunction "1_1") (pintype "passive"))
      (node (ref "xl") (pin "2") (pinfunction "FB_2") (pintype "passive"))
    )
    (net (code "63") (name "Net-(xl-VC)") (class "Default")
      (node (ref "C4") (pin "2") (pinfunction "2_2") (pintype "passive"))
      (node (ref "xl") (pin "4") (pinfunction "VC_4") (pintype "passive"))
    )
    (net (code "64") (name "VCC-3.3") (class "Default")
      (node (ref "2") (pin "2") (pinfunction "2_2") (pintype "passive"))
      (node (ref "2") (pin "4") (pinfunction "4_4") (pintype "passive"))
      (node (ref "C10") (pin "2") (pinfunction "2_2") (pintype "passive"))
      (node (ref "LM1") (pin "5") (pinfunction "Vout_5") (pintype "passive"))
      (node (ref "NLED1") (pin "1") (pinfunction "A_1") (pintype "passive"))
      (node (ref "P1") (pin "2") (pinfunction "2_2") (pintype "passive"))
      (node (ref "P2") (pin "3") (pinfunction "3_3") (pintype "passive"))
      (node (ref "P3") (pin "3") (pinfunction "3_3") (pintype "passive"))
      (node (ref "PLED1") (pin "1") (pinfunction "A_1") (pintype "passive"))
      (node (ref "Q1") (pin "2") (pinfunction "E_2") (pintype "passive"))
      (node (ref "R6") (pin "1") (pinfunction "1_1") (pintype "passive"))
      (node (ref "R7") (pin "1") (pinfunction "1_1") (pintype "passive"))
      (node (ref "R_RST1") (pin "1") (pinfunction "1_1") (pintype "passive"))
      (node (ref "STM32C8T6") (pin "1") (pinfunction "VBAT_1") (pintype "power_in"))
      (node (ref "STM32C8T6") (pin "24") (pinfunction "VDD_1_24") (pintype "power_in"))
      (node (ref "STM32C8T6") (pin "36") (pinfunction "VDD_2_36") (pintype "power_in"))
      (node (ref "STM32C8T6") (pin "48") (pinfunction "VDD_3_48") (pintype "power_in"))
      (node (ref "STM32C8T6") (pin "9") (pinfunction "VDDA_9") (pintype "power_in"))
      (node (ref "W1") (pin "3") (pinfunction "WP_3") (pintype "passive"))
      (node (ref "W1") (pin "7") (pinfunction "HOLD_7") (pintype "passive"))
      (node (ref "W1") (pin "8") (pinfunction "VCC_8") (pintype "passive"))
    )
    (net (code "65") (name "VCC-5.0") (class "Default")
      (node (ref "3") (pin "1") (pinfunction "1_1") (pintype "passive"))
      (node (ref "3") (pin "3") (pinfunction "3_3") (pintype "passive"))
      (node (ref "3") (pin "5") (pinfunction "5_5") (pintype "passive"))
      (node (ref "C1") (pin "2") (pinfunction "2_2") (pintype "passive"))
      (node (ref "C11") (pin "2") (pinfunction "2_2") (pintype "passive"))
      (node (ref "C17") (pin "2") (pinfunction "2_2") (pintype "passive"))
      (node (ref "C6") (pin "2") (pinfunction "2_2") (pintype "passive"))
      (node (ref "CG1") (pin "2") (pinfunction "2_2") (pintype "passive"))
      (node (ref "CG2") (pin "2") (pinfunction "2_2") (pintype "passive"))
      (node (ref "CG3") (pin "2") (pinfunction "2_2") (pintype "passive"))
      (node (ref "I1") (pin "4") (pinfunction "4_4") (pintype "passive"))
      (node (ref "LM1") (pin "1") (pinfunction "Vin_1") (pintype "passive"))
      (node (ref "R3") (pin "1") (pinfunction "1_1") (pintype "passive"))
      (node (ref "SER1") (pin "4") (pinfunction "4_4") (pintype "passive"))
      (node (ref "SER2") (pin "4") (pinfunction "4_4") (pintype "passive"))
      (node (ref "U5V0") (pin "2") (pinfunction "Vout_2") (pintype "passive"))
      (node (ref "USBVCC1") (pin "2") (pinfunction "2_2") (pintype "passive"))
    )
    (net (code "66") (name "VCC-IN") (class "Default")
      (node (ref "C2") (pin "1") (pinfunction "1_1") (pintype "passive"))
      (node (ref "C3") (pin "1") (pinfunction "1_1") (pintype "passive"))
      (node (ref "C4") (pin "1") (pinfunction "1_1") (pintype "passive"))
      (node (ref "P2") (pin "1") (pinfunction "1_1") (pintype "passive"))
      (node (ref "P3") (pin "1") (pinfunction "1_1") (pintype "passive"))
      (node (ref "SS54") (pin "1") (pinfunction "A_1") (pintype "passive"))
      (node (ref "SW1") (pin "2") (pinfunction "2_2") (pintype "passive"))
      (node (ref "xl") (pin "5") (pinfunction "VIN_5") (pintype "passive"))
    )
    (net (code "67") (name "VDJ") (class "Default")
      (node (ref "1") (pin "3") (pinfunction "3_3") (pintype "passive"))
      (node (ref "C7") (pin "1") (pinfunction "1_1") (pintype "passive"))
      (node (ref "C8") (pin "1") (pinfunction "1_1") (pintype "passive"))
      (node (ref "C9") (pin "1") (pinfunction "1_1") (pintype "passive"))
      (node (ref "DJ1") (pin "2") (pinfunction "2_2") (pintype "passive"))
      (node (ref "DJ2") (pin "2") (pinfunction "2_2") (pintype "passive"))
      (node (ref "DJ3") (pin "2") (pinfunction "2_2") (pintype "passive"))
      (node (ref "DJ4") (pin "2") (pinfunction "2_2") (pintype "passive"))
      (node (ref "DJ5") (pin "2") (pinfunction "2_2") (pintype "passive"))
      (node (ref "DJ6") (pin "2") (pinfunction "2_2") (pintype "passive"))
      (node (ref "L1") (pin "1") (pinfunction "1_1") (pintype "passive"))
    )
    (net (code "68") (name "VIN") (class "Default")
      (node (ref "C5") (pin "2") (pinfunction "2_2") (pintype "passive"))
      (node (ref "R4") (pin "1") (pinfunction "1_1") (pintype "passive"))
      (node (ref "SS54") (pin "2") (pinfunction "K_2") (pintype "passive"))
      (node (ref "U5V0") (pin "3") (pinfunction "Vin_3") (pintype "passive"))
    )
    (net (code "69") (name "unconnected-(CH1-CTS#-Pad9)") (class "Default")
      (node (ref "CH1") (pin "9") (pinfunction "CTS#_9") (pintype "passive"))
    )
    (net (code "70") (name "unconnected-(CH1-DCD#-Pad12)") (class "Default")
      (node (ref "CH1") (pin "12") (pinfunction "DCD#_12") (pintype "passive"))
    )
    (net (code "71") (name "unconnected-(CH1-DSR#-Pad10)") (class "Default")
      (node (ref "CH1") (pin "10") (pinfunction "DSR#_10") (pintype "passive"))
    )
    (net (code "72") (name "unconnected-(CH1-R232-Pad15)") (class "Default")
      (node (ref "CH1") (pin "15") (pinfunction "R232_15") (pintype "passive"))
    )
    (net (code "73") (name "unconnected-(CH1-RI#-Pad11)") (class "Default")
      (node (ref "CH1") (pin "11") (pinfunction "RI#_11") (pintype "passive"))
    )
    (net (code "74") (name "unconnected-(LM1-NC-Pad4)") (class "Default")
      (node (ref "LM1") (pin "4") (pinfunction "NC_4") (pintype "passive+no_connect"))
    )
    (net (code "75") (name "unconnected-(M1-Pad1)") (class "Default")
      (node (ref "M1") (pin "1") (pinfunction "1_1") (pintype "passive"))
    )
    (net (code "76") (name "unconnected-(M2-Pad1)") (class "Default")
      (node (ref "M2") (pin "1") (pinfunction "1_1") (pintype "passive"))
    )
    (net (code "77") (name "unconnected-(M3-Pad1)") (class "Default")
      (node (ref "M3") (pin "1") (pinfunction "1_1") (pintype "passive"))
    )
    (net (code "78") (name "unconnected-(M4-Pad1)") (class "Default")
      (node (ref "M4") (pin "1") (pinfunction "1_1") (pintype "passive"))
    )
    (net (code "79") (name "unconnected-(MUSB1-ID-Pad4)") (class "Default")
      (node (ref "MUSB1") (pin "4") (pinfunction "ID_4") (pintype "passive"))
    )
    (net (code "80") (name "unconnected-(STM32C8T6-PC13-TAMPER-RTC-Pad2)") (class "Default")
      (node (ref "STM32C8T6") (pin "2") (pinfunction "PC13-TAMPER-RTC_2") (pintype "bidirectional+no_connect"))
    )
    (net (code "81") (name "unconnected-(STM32C8T6-PC14-OSC32_IN-Pad3)") (class "Default")
      (node (ref "STM32C8T6") (pin "3") (pinfunction "PC14-OSC32_IN_3") (pintype "bidirectional+no_connect"))
    )
    (net (code "82") (name "unconnected-(STM32C8T6-PC15-OSC32_OUT-Pad4)") (class "Default")
      (node (ref "STM32C8T6") (pin "4") (pinfunction "PC15-OSC32_OUT_4") (pintype "bidirectional+no_connect"))
    )
    (net (code "83") (name "unconnected-(SW1-Pad3)") (class "Default")
      (node (ref "SW1") (pin "3") (pinfunction "3_3") (pintype "passive"))
    )
    (net (code "84") (name "unconnected-(USBVCC1-Pad1)") (class "Default")
      (node (ref "USBVCC1") (pin "1") (pinfunction "1_1") (pintype "passive"))
    )
  )
)
